# Sheet2.net
KiCad netlist of a schematic drawn in Altium Designer
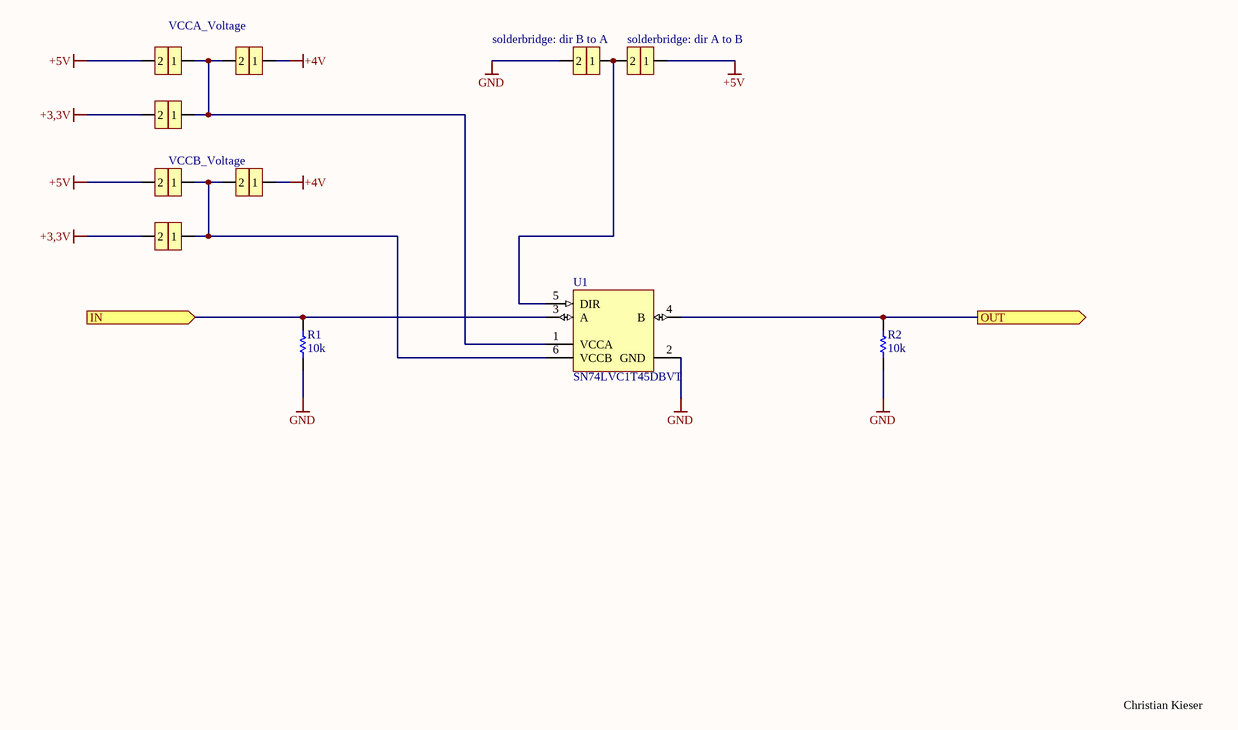
[diagram p0: Sheet2.SchDoc]

(export (version "E")
  (design (tool "Eeschema 10.0.6"))
  (components
    (comp (ref "J1")
      (value "normal solderbridge")
      (footprint "PCBComponent")
      (libsource (lib "Altium Vault EMBL 3") (part "CMP-001-0133-A.1"))
    )
    (comp (ref "J2")
      (value "normal solderbridge")
      (footprint "PCBComponent")
      (libsource (lib "Altium Vault EMBL 3") (part "CMP-001-0133-A.1"))
    )
    (comp (ref "J3")
      (value "normal solderbridge")
      (footprint "PCBComponent")
      (libsource (lib "Altium Vault EMBL 3") (part "CMP-001-0133-A.1"))
    )
    (comp (ref "J4")
      (value "normal solderbridge")
      (footprint "PCBComponent")
      (libsource (lib "Altium Vault EMBL 3") (part "CMP-001-0133-A.1"))
    )
    (comp (ref "J5")
      (value "normal solderbridge")
      (footprint "PCBComponent")
      (libsource (lib "Altium Vault EMBL 3") (part "CMP-001-0133-A.1"))
    )
    (comp (ref "J6")
      (value "normal solderbridge")
      (footprint "PCBComponent")
      (libsource (lib "Altium Vault EMBL 3") (part "CMP-001-0133-A.1"))
    )
    (comp (ref "J7")
      (value "normal solderbridge")
      (footprint "PCBComponent")
      (libsource (lib "Altium Vault EMBL 3") (part "CMP-001-0133-A.1"))
    )
    (comp (ref "J8")
      (value "normal solderbridge")
      (footprint "PCBComponent")
      (libsource (lib "Altium Vault EMBL 3") (part "CMP-001-0133-A.1"))
    )
    (comp (ref "R1")
      (value "10k")
      (footprint "YAGO-RC0805_M")
      (description "0805 Yageo Standard BlackBox Resistors")
      (fields (field (name "TOLERANCE") "±1%") (field (name "MANUFACTURER") "Yageo"))
      (libsource (lib "Altium Vault EMBL 3") (part "CMP-001-0027-2"))
    )
    (comp (ref "R2")
      (value "10k")
      (footprint "YAGO-RC0805_M")
      (description "0805 Yageo Standard BlackBox Resistors")
      (fields (field (name "TOLERANCE") "±1%") (field (name "MANUFACTURER") "Yageo"))
      (libsource (lib "Altium Vault EMBL") (part "CMP-001-0027-2"))
    )
    (comp (ref "U1")
      (value "SN74LVC1T45DBVT")
      (footprint "DBV0006A_M")
      (fields
        (field (name "MANUFACTURER") "Texas Instruments")
        (field (name "GENERIC PART NUMBER") "SN74LVC1T45")
        (field (name "PARTNUMBER") "SN74LVC1T45DBVTG4")
      )
      (libsource (lib "Altium Vault EMBL 3") (part "TI-SN74XVC1T45-6"))
    )
  )
  (nets
    (net (code "1") (name "+3,3V") (class "Default")
      (node (ref "J3") (pin "2") (pinfunction "2_2") (pintype "passive"))
      (node (ref "J6") (pin "2") (pinfunction "2_2") (pintype "passive"))
    )
    (net (code "2") (name "+4V") (class "Default")
      (node (ref "J2") (pin "1") (pinfunction "1_1") (pintype "passive"))
      (node (ref "J5") (pin "1") (pinfunction "1_1") (pintype "passive"))
    )
    (net (code "3") (name "+5V") (class "Default")
      (node (ref "J1") (pin "2") (pinfunction "2_2") (pintype "passive"))
      (node (ref "J4") (pin "2") (pinfunction "2_2") (pintype "passive"))
      (node (ref "J8") (pin "1") (pinfunction "1_1") (pintype "passive"))
    )
    (net (code "4") (name "/IN") (class "Default")
      (node (ref "R1") (pin "2") (pinfunction "2_2") (pintype "passive"))
      (node (ref "U1") (pin "3") (pinfunction "A_3") (pintype "bidirectional"))
    )
    (net (code "5") (name "/OUT") (class "Default")
      (node (ref "R2") (pin "2") (pinfunction "2_2") (pintype "passive"))
      (node (ref "U1") (pin "4") (pinfunction "B_4") (pintype "bidirectional"))
    )
    (net (code "6") (name "GND") (class "Default")
      (node (ref "J7") (pin "2") (pinfunction "2_2") (pintype "passive"))
      (node (ref "R1") (pin "1") (pinfunction "1_1") (pintype "passive"))
      (node (ref "R2") (pin "1") (pinfunction "1_1") (pintype "passive"))
      (node (ref "U1") (pin "2") (pinfunction "GND_2") (pintype "power_in"))
    )
    (net (code "7") (name "Net-(U1-DIR)") (class "Default")
      (node (ref "J7") (pin "1") (pinfunction "1_1") (pintype "passive"))
      (node (ref "J8") (pin "2") (pinfunction "2_2") (pintype "passive"))
      (node (ref "U1") (pin "5") (pinfunction "DIR_5") (pintype "input"))
    )
    (net (code "8") (name "Net-(U1-VCCA)") (class "Default")
      (node (ref "J1") (pin "1") (pinfunction "1_1") (pintype "passive"))
      (node (ref "J2") (pin "2") (pinfunction "2_2") (pintype "passive"))
      (node (ref "J3") (pin "1") (pinfunction "1_1") (pintype "passive"))
      (node (ref "U1") (pin "1") (pinfunction "VCCA_1") (pintype "power_in"))
    )
    (net (code "9") (name "Net-(U1-VCCB)") (class "Default")
      (node (ref "J4") (pin "1") (pinfunction "1_1") (pintype "passive"))
      (node (ref "J5") (pin "2") (pinfunction "2_2") (pintype "passive"))
      (node (ref "J6") (pin "1") (pinfunction "1_1") (pintype "passive"))
      (node (ref "U1") (pin "6") (pinfunction "VCCB_6") (pintype "power_in"))
    )
  )
)
